# FSKube.net
KiCad netlist of a schematic drawn in EAGLE
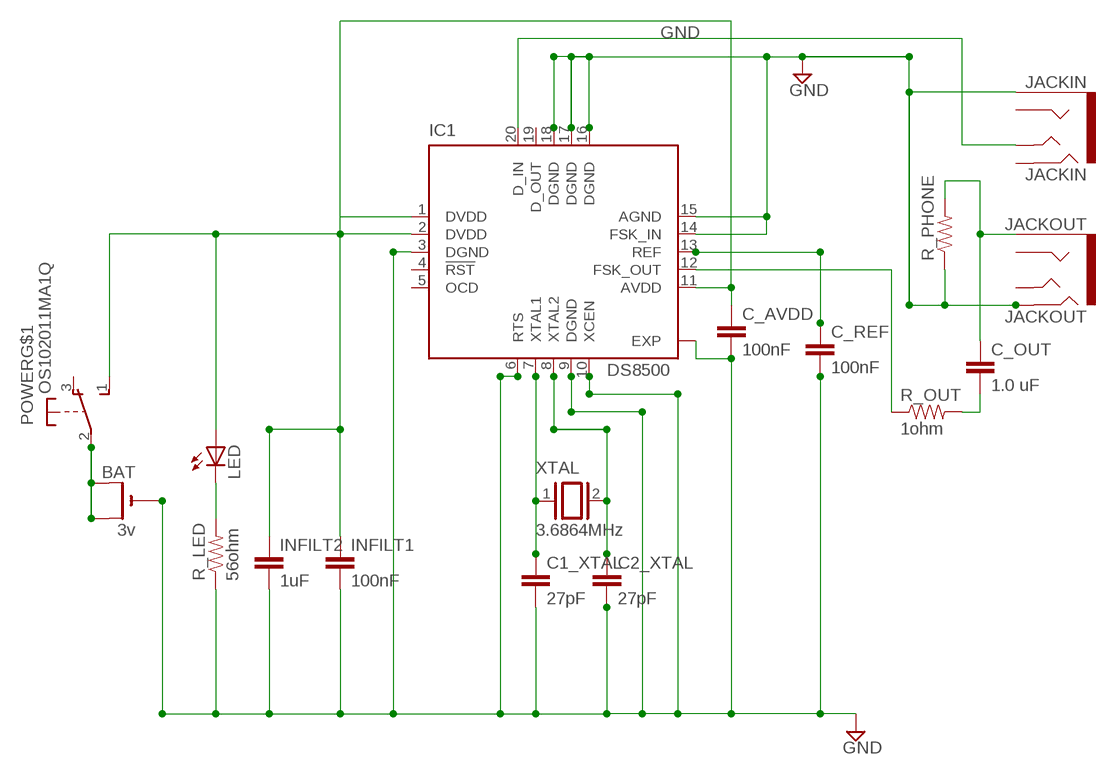
[diagram p0: schematic, sheet 1]

(export (version "E")
  (design (tool "Eeschema 10.0.6"))
  (components
    (comp (ref "BAT")
      (value "3v")
      (footprint "eagle-import:CR1220-THM")
      (libsource (lib "eagle-import") (part "CR1220THM"))
    )
    (comp (ref "C1_XTAL")
      (value "27pF")
      (footprint "eagle-import:C2.5-2")
      (libsource (lib "eagle-import") (part "C2.5/2"))
    )
    (comp (ref "C2_XTAL")
      (value "27pF")
      (footprint "eagle-import:C2.5-2")
      (libsource (lib "eagle-import") (part "C2.5/2"))
    )
    (comp (ref "C_AVDD")
      (value "100nF")
      (footprint "eagle-import:C2.5-2")
      (libsource (lib "eagle-import") (part "C2.5/2"))
    )
    (comp (ref "C_OUT")
      (value "1.0 uF")
      (footprint "eagle-import:C2.5-2")
      (libsource (lib "eagle-import") (part "C2.5/2"))
    )
    (comp (ref "C_REF")
      (value "100nF")
      (footprint "eagle-import:C2.5-2")
      (libsource (lib "eagle-import") (part "C2.5/2"))
    )
    (comp (ref "IC1")
      (value "DS8500")
      (footprint "eagle-import:TQFN20-5X5")
      (fields (field (name "MPN") "DS8500-JND+"))
      (libsource (lib "eagle-import") (part "DS8500"))
    )
    (comp (ref "INFILT1")
      (value "100nF")
      (footprint "eagle-import:C2.5-2")
      (libsource (lib "eagle-import") (part "C2.5/2"))
    )
    (comp (ref "INFILT2")
      (value "1uF")
      (footprint "eagle-import:C2.5-2")
      (libsource (lib "eagle-import") (part "C2.5/2"))
    )
    (comp (ref "JACKIN")
      (value "JACKIN")
      (footprint "eagle-import:AUDIO-JACK-TRRS-SMD")
      (libsource (lib "eagle-import") (part "AUDIO-JACK3"))
    )
    (comp (ref "JACKOUT")
      (value "JACKOUT")
      (footprint "eagle-import:AUDIO-JACK-TRRS-SMD")
      (libsource (lib "eagle-import") (part "AUDIO-JACK3"))
    )
    (comp (ref "LED")
      (value "LED3MM")
      (footprint "eagle-import:LED3MM")
      (libsource (lib "eagle-import") (part "LED3MM"))
    )
    (comp (ref "POWER")
      (value "OS102011MA1Q")
      (footprint "eagle-import:OS102011MA1Q")
      (libsource (lib "eagle-import") (part "OS102011MA1Q"))
    )
    (comp (ref "R_LED")
      (value "56ohm")
      (footprint "eagle-import:1_6W-RES")
      (libsource (lib "eagle-import") (part "RESISTORPTH-1/6W"))
    )
    (comp (ref "R_OUT")
      (value "1ohm")
      (footprint "eagle-import:1_6W-RES")
      (libsource (lib "eagle-import") (part "RESISTORPTH-1/6W"))
    )
    (comp (ref "R_PHONE")
      (value "RESISTORPTH-1/6W")
      (footprint "eagle-import:1_6W-RES")
      (libsource (lib "eagle-import") (part "RESISTORPTH-1/6W"))
    )
    (comp (ref "XTAL")
      (value "3.6864MHz")
      (footprint "eagle-import:QS")
      (libsource (lib "eagle-import") (part "XTAL/S"))
    )
  )
  (nets
    (net (code "1") (name "GND") (class "Default")
      (node (ref "BAT") (pin "-") (pinfunction "-_-") (pintype "passive"))
      (node (ref "C1_XTAL") (pin "2") (pinfunction "2_2") (pintype "passive"))
      (node (ref "C2_XTAL") (pin "2") (pinfunction "2_2") (pintype "passive"))
      (node (ref "C_AVDD") (pin "2") (pinfunction "2_2") (pintype "passive"))
      (node (ref "C_REF") (pin "2") (pinfunction "2_2") (pintype "passive"))
      (node (ref "IC1") (pin "10") (pinfunction "XCEN_10") (pintype "input"))
      (node (ref "IC1") (pin "14") (pinfunction "FSK_IN_14") (pintype "input"))
      (node (ref "IC1") (pin "15") (pinfunction "AGND_15") (pintype "input"))
      (node (ref "IC1") (pin "16") (pinfunction "DGND_16") (pintype "power_in"))
      (node (ref "IC1") (pin "17") (pinfunction "DGND_17") (pintype "power_in"))
      (node (ref "IC1") (pin "18") (pinfunction "DGND_18") (pintype "power_in"))
      (node (ref "IC1") (pin "3") (pinfunction "DGND_3") (pintype "power_in"))
      (node (ref "IC1") (pin "6") (pinfunction "RTS_6") (pintype "input"))
      (node (ref "IC1") (pin "9") (pinfunction "DGND_9") (pintype "power_in"))
      (node (ref "IC1") (pin "EXP") (pinfunction "EXP_EXP") (pintype "passive"))
      (node (ref "INFILT1") (pin "2") (pinfunction "2_2") (pintype "passive"))
      (node (ref "INFILT2") (pin "2") (pinfunction "2_2") (pintype "passive"))
      (node (ref "JACKIN") (pin "EARTH") (pinfunction "EARTH_EARTH") (pintype "bidirectional"))
      (node (ref "JACKOUT") (pin "RING2") (pinfunction "RING2_RING2") (pintype "bidirectional"))
      (node (ref "R_LED") (pin "1") (pinfunction "1_1") (pintype "passive"))
      (node (ref "R_PHONE") (pin "1") (pinfunction "1_1") (pintype "passive"))
    )
    (net (code "2") (name "Net-(BAT-+)") (class "Default")
      (node (ref "BAT") (pin "+1") (pinfunction "+_+1") (pintype "passive"))
      (node (ref "BAT") (pin "+2") (pinfunction "+1_+2") (pintype "passive"))
      (node (ref "POWER") (pin "2") (pinfunction "P_2") (pintype "passive"))
    )
    (net (code "3") (name "Net-(C_OUT-Pad1)") (class "Default")
      (node (ref "C_OUT") (pin "1") (pinfunction "1_1") (pintype "passive"))
      (node (ref "JACKOUT") (pin "EARTH") (pinfunction "EARTH_EARTH") (pintype "bidirectional"))
      (node (ref "R_PHONE") (pin "2") (pinfunction "2_2") (pintype "passive"))
    )
    (net (code "4") (name "Net-(C_OUT-Pad2)") (class "Default")
      (node (ref "C_OUT") (pin "2") (pinfunction "2_2") (pintype "passive"))
      (node (ref "R_OUT") (pin "2") (pinfunction "2_2") (pintype "passive"))
    )
    (net (code "5") (name "Net-(IC1-AVDD)") (class "Default")
      (node (ref "C_AVDD") (pin "1") (pinfunction "1_1") (pintype "passive"))
      (node (ref "IC1") (pin "1") (pinfunction "DVDD_1") (pintype "power_in"))
      (node (ref "IC1") (pin "11") (pinfunction "AVDD_11") (pintype "input"))
      (node (ref "IC1") (pin "2") (pinfunction "DVDD_2") (pintype "power_in"))
      (node (ref "INFILT1") (pin "1") (pinfunction "1_1") (pintype "passive"))
      (node (ref "INFILT2") (pin "1") (pinfunction "1_1") (pintype "passive"))
      (node (ref "LED") (pin "A") (pinfunction "A_A") (pintype "passive"))
      (node (ref "POWER") (pin "1") (pinfunction "S_1") (pintype "passive"))
    )
    (net (code "6") (name "Net-(IC1-D_IN)") (class "Default")
      (node (ref "IC1") (pin "20") (pinfunction "D_IN_20") (pintype "input"))
      (node (ref "JACKIN") (pin "TIP") (pinfunction "TIP_TIP") (pintype "bidirectional"))
    )
    (net (code "7") (name "Net-(IC1-FSK_OUT)") (class "Default")
      (node (ref "IC1") (pin "12") (pinfunction "FSK_OUT_12") (pintype "output"))
      (node (ref "R_OUT") (pin "1") (pinfunction "1_1") (pintype "passive"))
    )
    (net (code "8") (name "Net-(IC1-REF)") (class "Default")
      (node (ref "C_REF") (pin "1") (pinfunction "1_1") (pintype "passive"))
      (node (ref "IC1") (pin "13") (pinfunction "REF_13") (pintype "output"))
    )
    (net (code "9") (name "Net-(IC1-XTAL1)") (class "Default")
      (node (ref "C1_XTAL") (pin "1") (pinfunction "1_1") (pintype "passive"))
      (node (ref "IC1") (pin "7") (pinfunction "XTAL1_7") (pintype "input"))
      (node (ref "XTAL") (pin "1") (pinfunction "1_1") (pintype "passive"))
    )
    (net (code "10") (name "Net-(IC1-XTAL2)") (class "Default")
      (node (ref "C2_XTAL") (pin "1") (pinfunction "1_1") (pintype "passive"))
      (node (ref "IC1") (pin "8") (pinfunction "XTAL2_8") (pintype "output"))
      (node (ref "XTAL") (pin "2") (pinfunction "2_2") (pintype "passive"))
    )
    (net (code "11") (name "Net-(LED-C)") (class "Default")
      (node (ref "LED") (pin "K") (pinfunction "C_K") (pintype "passive"))
      (node (ref "R_LED") (pin "2") (pinfunction "2_2") (pintype "passive"))
    )
    (net (code "12") (name "unconnected-(IC1-D_OUT-Pad19)") (class "Default")
      (node (ref "IC1") (pin "19") (pinfunction "D_OUT_19") (pintype "output"))
    )
    (net (code "13") (name "unconnected-(IC1-OCD-Pad5)") (class "Default")
      (node (ref "IC1") (pin "5") (pinfunction "OCD_5") (pintype "output"))
    )
    (net (code "14") (name "unconnected-(IC1-~{RST}-Pad4)") (class "Default")
      (node (ref "IC1") (pin "4") (pinfunction "~{RST}_4") (pintype "bidirectional"))
    )
    (net (code "15") (name "unconnected-(JACKIN-PadRING1)") (class "Default")
      (node (ref "JACKIN") (pin "RING1") (pinfunction "RING1_RING1") (pintype "bidirectional"))
    )
    (net (code "16") (name "unconnected-(JACKIN-PadRING2)") (class "Default")
      (node (ref "JACKIN") (pin "RING2") (pinfunction "RING2_RING2") (pintype "bidirectional"))
    )
    (net (code "17") (name "unconnected-(JACKOUT-PadRING1)") (class "Default")
      (node (ref "JACKOUT") (pin "RING1") (pinfunction "RING1_RING1") (pintype "bidirectional"))
    )
    (net (code "18") (name "unconnected-(JACKOUT-PadTIP)") (class "Default")
      (node (ref "JACKOUT") (pin "TIP") (pinfunction "TIP_TIP") (pintype "bidirectional"))
    )
    (net (code "19") (name "unconnected-(POWERA-O-Pad3)") (class "Default")
      (node (ref "POWER") (pin "3") (pinfunction "O_3") (pintype "passive"))
    )
  )
)
